# mbed-enablement-platform_F_2.net
KiCad netlist of a schematic drawn in Altium Designer
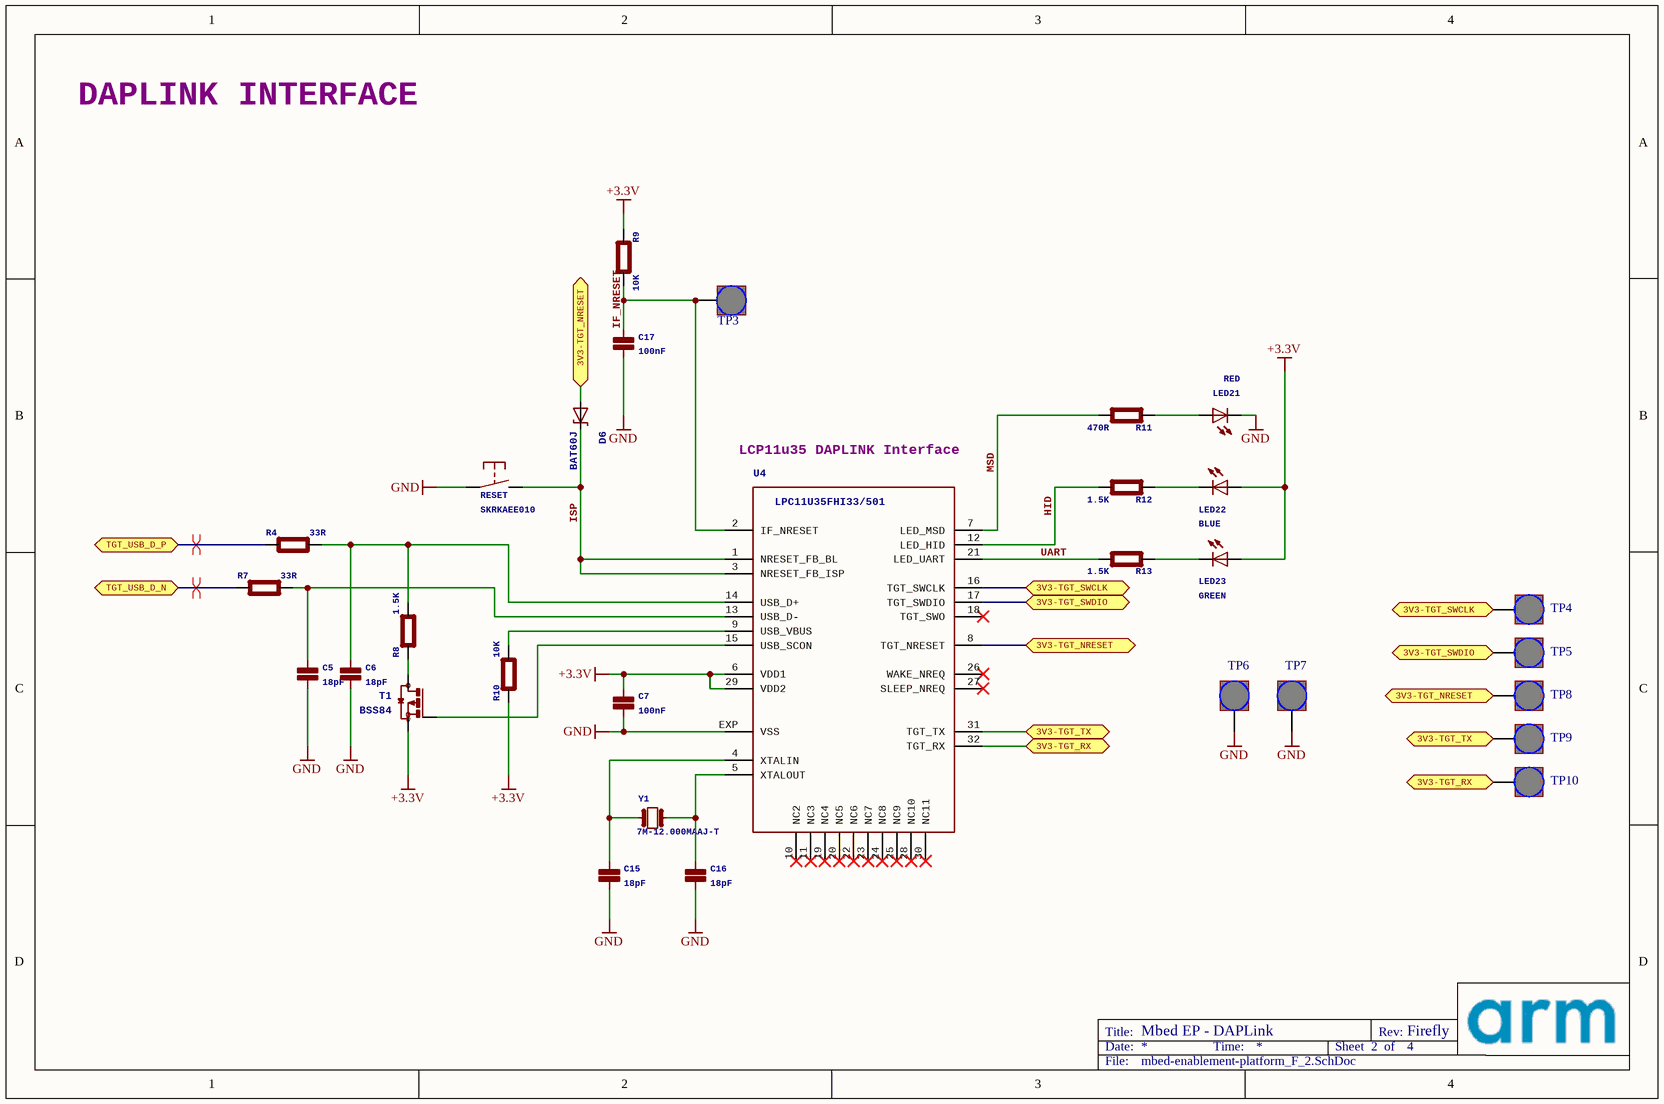
[diagram p0: mbed-enablement-platform_F_2.SchDoc]

(export (version "E")
  (design (tool "Eeschema 10.0.6"))
  (components
    (comp (ref "C5")
      (value "18pF")
      (footprint "0402")
      (description "Capacitor")
      (libsource (lib "mbed-workplace-env-mon") (part "CAPACITOR0402"))
    )
    (comp (ref "C6")
      (value "18pF")
      (footprint "0402")
      (description "Capacitor")
      (libsource (lib "mbed-workplace-env-mon") (part "CAPACITOR0402"))
    )
    (comp (ref "C7")
      (value "100nF")
      (footprint "0402")
      (description "Capacitor")
      (libsource (lib "mbed-workplace-env-mon") (part "CAPACITOR0402"))
    )
    (comp (ref "C15")
      (value "18pF")
      (footprint "0402")
      (description "Capacitor")
      (libsource (lib "mbed-workplace-env-mon") (part "CAPACITOR0402"))
    )
    (comp (ref "C16")
      (value "18pF")
      (footprint "0402")
      (description "Capacitor")
      (libsource (lib "mbed-workplace-env-mon") (part "CAPACITOR0402"))
    )
    (comp (ref "C17")
      (value "100nF")
      (footprint "0402")
      (description "Capacitor")
      (libsource (lib "mbed-workplace-env-mon") (part "CAPACITOR0402"))
    )
    (comp (ref "D6")
      (value "BAT60J")
      (footprint "SOD323")
      (description "SCHOTTKY DIODE")
      (fields (field (name "MF") "STMicroelectronics"))
      (libsource (lib "mbed-workplace-env-mon") (part "BAT60J"))
    )
    (comp (ref "LED21")
      (value "RED")
      (footprint "CHIPLED_0603")
      (description "LED SMD, Colour Red")
      (fields (field (name "MF") "Wurth Electronics Inc"))
      (libsource (lib "mbed-workplace-env-mon") (part "SMD_LED0603"))
    )
    (comp (ref "LED22")
      (value "BLUE")
      (footprint "CHIPLED_0603")
      (description "LED SMD, Colour Red")
      (fields (field (name "MF") "Wurth Electronics Inc"))
      (libsource (lib "mbed-workplace-env-mon") (part "SMD_LED0603"))
    )
    (comp (ref "LED23")
      (value "GREEN")
      (footprint "CHIPLED_0603")
      (description "LED SMD, Colour Red")
      (fields (field (name "MF") "Wurth Electronics Inc"))
      (libsource (lib "mbed-workplace-env-mon") (part "SMD_LED0603"))
    )
    (comp (ref "R4")
      (value "33R")
      (footprint "0402")
      (description "Resistor")
      (libsource (lib "mbed-workplace-env-mon") (part "RESISTOR0402"))
    )
    (comp (ref "R7")
      (value "33R")
      (footprint "0402")
      (description "Resistor")
      (libsource (lib "mbed-workplace-env-mon") (part "RESISTOR0402"))
    )
    (comp (ref "R8")
      (value "1.5K")
      (footprint "0402")
      (description "Resistor")
      (libsource (lib "mbed-workplace-env-mon") (part "RESISTOR0402"))
    )
    (comp (ref "R9")
      (value "10K")
      (footprint "0402")
      (description "Resistor")
      (libsource (lib "mbed-workplace-env-mon") (part "RESISTOR0402"))
    )
    (comp (ref "R10")
      (value "10K")
      (footprint "0402")
      (description "Resistor")
      (libsource (lib "mbed-workplace-env-mon") (part "RESISTOR0402"))
    )
    (comp (ref "R11")
      (value "470R")
      (footprint "0402")
      (description "Resistor")
      (libsource (lib "mbed-workplace-env-mon") (part "RESISTOR0402"))
    )
    (comp (ref "R12")
      (value "1.5K")
      (footprint "0402")
      (description "Resistor")
      (libsource (lib "mbed-workplace-env-mon") (part "RESISTOR0402"))
    )
    (comp (ref "R13")
      (value "1.5K")
      (footprint "0402")
      (description "Resistor")
      (libsource (lib "mbed-workplace-env-mon") (part "RESISTOR0402"))
    )
    (comp (ref "RESET")
      (value "SKRKAEE010")
      (footprint "SKRKAEE010")
      (description "MOMENTARY SWITCH PUSH VERTICAL (SPST)")
      (fields (field (name "MF") "ALPS"))
      (libsource (lib "mbed-workplace-env-mon") (part "SKRKAEE010"))
    )
    (comp (ref "T1")
      (value "BSS84")
      (footprint "SOT23-3")
      (description "MOSFET P-CHANNEL")
      (fields (field (name "MF") "Fairchild Semiconductor"))
      (libsource (lib "mbed-workplace-env-mon") (part "BSS84"))
    )
    (comp (ref "TP3")
      (value "TP, 1.5mm")
      (footprint "TP1.5")
      (description "1.5mm round test point")
      (libsource (lib "mbed-workplace-env-mon") (part "TP1.5"))
    )
    (comp (ref "TP4")
      (value "TP, 1.5mm")
      (footprint "TP1.5")
      (description "1.5mm round test point")
      (libsource (lib "mbed-workplace-env-mon") (part "TP1.5"))
    )
    (comp (ref "TP5")
      (value "TP, 1.5mm")
      (footprint "TP1.5")
      (description "1.5mm round test point")
      (libsource (lib "mbed-workplace-env-mon") (part "TP1.5"))
    )
    (comp (ref "TP6")
      (value "TP, 1.5mm")
      (footprint "TP1.5")
      (description "1.5mm round test point")
      (libsource (lib "mbed-workplace-env-mon") (part "TP1.5"))
    )
    (comp (ref "TP7")
      (value "TP, 1.5mm")
      (footprint "TP1.5")
      (description "1.5mm round test point")
      (libsource (lib "mbed-workplace-env-mon") (part "TP1.5"))
    )
    (comp (ref "TP8")
      (value "TP, 1.5mm")
      (footprint "TP1.5")
      (description "1.5mm round test point")
      (libsource (lib "mbed-workplace-env-mon") (part "TP1.5"))
    )
    (comp (ref "TP9")
      (value "TP, 1.5mm")
      (footprint "TP1.5")
      (description "1.5mm round test point")
      (libsource (lib "mbed-workplace-env-mon") (part "TP1.5"))
    )
    (comp (ref "TP10")
      (value "TP, 1.5mm")
      (footprint "TP1.5")
      (description "1.5mm round test point")
      (libsource (lib "mbed-workplace-env-mon") (part "TP1.5"))
    )
    (comp (ref "U4")
      (value "IF_LPC11U35FHI33/501")
      (footprint "HVQFN33")
      (description "CMSIS-DAP Interface : 32-bit LPC11U00 ARM Cortex M3 RISC 64KB Flash 2.5V/3.3V 33-Pin HVQFN EP")
      (fields (field (name "MF") "NXP") (field (name "LPC11U35FHI33/501") "LPC11U35FHI33/501"))
      (libsource (lib "mbed-workplace-env-mon") (part "IF_LPC11U35FHI33/501"))
    )
    (comp (ref "Y1")
      (value "7M-12.000MAAJ-T")
      (footprint "3.2X.2.5")
      (description "Crystal, TXC 12MHz Â±30ppm 18pF")
      (fields (field (name "MF") "TXC"))
      (libsource (lib "mbed-workplace-env-mon") (part "7M-12.000MAAJ-T"))
    )
  )
  (nets
    (net (code "1") (name "+3.3V") (class "Default")
      (node (ref "C7") (pin "1") (pinfunction "P$1_1") (pintype "passive"))
      (node (ref "LED22") (pin "A") (pinfunction "A_A") (pintype "passive"))
      (node (ref "LED23") (pin "A") (pinfunction "A_A") (pintype "passive"))
      (node (ref "R10") (pin "1") (pinfunction "P$1_1") (pintype "passive"))
      (node (ref "R9") (pin "1") (pinfunction "P$1_1") (pintype "passive"))
      (node (ref "T1") (pin "2") (pinfunction "S_2") (pintype "passive"))
      (node (ref "U4") (pin "29") (pinfunction "VDD2_29") (pintype "passive"))
      (node (ref "U4") (pin "6") (pinfunction "VDD1_6") (pintype "passive"))
    )
    (net (code "2") (name "/3V3-TGT_NRESET") (class "Default")
      (node (ref "D6") (pin "A") (pinfunction "A_A") (pintype "passive"))
      (node (ref "TP8") (pin "1") (pinfunction "1_1") (pintype "passive"))
      (node (ref "U4") (pin "8") (pinfunction "TGT_NRESET_8") (pintype "passive"))
    )
    (net (code "3") (name "/3V3-TGT_RX") (class "Default")
      (node (ref "TP10") (pin "1") (pinfunction "1_1") (pintype "passive"))
      (node (ref "U4") (pin "32") (pinfunction "TGT_RX_32") (pintype "passive"))
    )
    (net (code "4") (name "/3V3-TGT_SWCLK") (class "Default")
      (node (ref "TP4") (pin "1") (pinfunction "1_1") (pintype "passive"))
      (node (ref "U4") (pin "16") (pinfunction "TGT_SWCLK_16") (pintype "passive"))
    )
    (net (code "5") (name "/3V3-TGT_SWDIO") (class "Default")
      (node (ref "TP5") (pin "1") (pinfunction "1_1") (pintype "passive"))
      (node (ref "U4") (pin "17") (pinfunction "TGT_SWDIO_17") (pintype "passive"))
    )
    (net (code "6") (name "/3V3-TGT_TX") (class "Default")
      (node (ref "TP9") (pin "1") (pinfunction "1_1") (pintype "passive"))
      (node (ref "U4") (pin "31") (pinfunction "TGT_TX_31") (pintype "passive"))
    )
    (net (code "7") (name "/HID") (class "Default")
      (node (ref "R12") (pin "2") (pinfunction "P$2_2") (pintype "passive"))
      (node (ref "U4") (pin "12") (pinfunction "LED_HID_12") (pintype "passive"))
    )
    (net (code "8") (name "/IF_NRESET") (class "Default")
      (node (ref "C17") (pin "1") (pinfunction "P$1_1") (pintype "passive"))
      (node (ref "R9") (pin "2") (pinfunction "P$2_2") (pintype "passive"))
      (node (ref "TP3") (pin "1") (pinfunction "1_1") (pintype "passive"))
      (node (ref "U4") (pin "2") (pinfunction "IF_NRESET_2") (pintype "passive"))
    )
    (net (code "9") (name "/ISP") (class "Default")
      (node (ref "D6") (pin "K") (pinfunction "K_K") (pintype "passive"))
      (node (ref "RESET") (pin "P$2") (pinfunction "S_P$2") (pintype "passive"))
      (node (ref "U4") (pin "1") (pinfunction "NRESET_FB_BL_1") (pintype "passive"))
      (node (ref "U4") (pin "3") (pinfunction "NRESET_FB_ISP_3") (pintype "passive"))
    )
    (net (code "10") (name "/MSD") (class "Default")
      (node (ref "R11") (pin "2") (pinfunction "P$2_2") (pintype "passive"))
      (node (ref "U4") (pin "7") (pinfunction "LED_MSD_7") (pintype "passive"))
    )
    (net (code "11") (name "/TGT_USB_D_N") (class "Default")
      (node (ref "R7") (pin "1") (pinfunction "P$1_1") (pintype "passive"))
    )
    (net (code "12") (name "/TGT_USB_D_P") (class "Default")
      (node (ref "R4") (pin "1") (pinfunction "P$1_1") (pintype "passive"))
    )
    (net (code "13") (name "/UART") (class "Default")
      (node (ref "R13") (pin "2") (pinfunction "P$2_2") (pintype "passive"))
      (node (ref "U4") (pin "21") (pinfunction "LED_UART_21") (pintype "passive"))
    )
    (net (code "14") (name "GND") (class "Default")
      (node (ref "C15") (pin "2") (pinfunction "P$2_2") (pintype "passive"))
      (node (ref "C16") (pin "2") (pinfunction "P$2_2") (pintype "passive"))
      (node (ref "C17") (pin "2") (pinfunction "P$2_2") (pintype "passive"))
      (node (ref "C5") (pin "2") (pinfunction "P$2_2") (pintype "passive"))
      (node (ref "C6") (pin "2") (pinfunction "P$2_2") (pintype "passive"))
      (node (ref "C7") (pin "2") (pinfunction "P$2_2") (pintype "passive"))
      (node (ref "LED21") (pin "C") (pinfunction "C_C") (pintype "passive"))
      (node (ref "RESET") (pin "P$1") (pinfunction "P_P$1") (pintype "passive"))
      (node (ref "TP6") (pin "1") (pinfunction "1_1") (pintype "passive"))
      (node (ref "TP7") (pin "1") (pinfunction "1_1") (pintype "passive"))
      (node (ref "U4") (pin "EXP") (pinfunction "VSS_EXP") (pintype "passive"))
    )
    (net (code "15") (name "Net-(C5-P$1)") (class "Default")
      (node (ref "C5") (pin "1") (pinfunction "P$1_1") (pintype "passive"))
      (node (ref "R7") (pin "2") (pinfunction "P$2_2") (pintype "passive"))
      (node (ref "U4") (pin "13") (pinfunction "USB_D-_13") (pintype "passive"))
    )
    (net (code "16") (name "Net-(C6-P$1)") (class "Default")
      (node (ref "C6") (pin "1") (pinfunction "P$1_1") (pintype "passive"))
      (node (ref "R4") (pin "2") (pinfunction "P$2_2") (pintype "passive"))
      (node (ref "R8") (pin "2") (pinfunction "P$2_2") (pintype "passive"))
      (node (ref "U4") (pin "14") (pinfunction "USB_D+_14") (pintype "passive"))
    )
    (net (code "17") (name "Net-(C15-P$1)") (class "Default")
      (node (ref "C15") (pin "1") (pinfunction "P$1_1") (pintype "passive"))
      (node (ref "U4") (pin "4") (pinfunction "XTALIN_4") (pintype "passive"))
      (node (ref "Y1") (pin "P$1") (pinfunction "1_P$1") (pintype "passive"))
    )
    (net (code "18") (name "Net-(C16-P$1)") (class "Default")
      (node (ref "C16") (pin "1") (pinfunction "P$1_1") (pintype "passive"))
      (node (ref "U4") (pin "5") (pinfunction "XTALOUT_5") (pintype "passive"))
      (node (ref "Y1") (pin "P$3") (pinfunction "2_P$3") (pintype "passive"))
    )
    (net (code "19") (name "Net-(R8-P$1)") (class "Default")
      (node (ref "R8") (pin "1") (pinfunction "P$1_1") (pintype "passive"))
      (node (ref "T1") (pin "3") (pinfunction "D_3") (pintype "passive"))
    )
    (net (code "20") (name "Net-(R10-P$2)") (class "Default")
      (node (ref "R10") (pin "2") (pinfunction "P$2_2") (pintype "passive"))
      (node (ref "U4") (pin "9") (pinfunction "USB_VBUS_9") (pintype "passive"))
    )
    (net (code "21") (name "Net-(R11-P$1)") (class "Default")
      (node (ref "LED21") (pin "A") (pinfunction "A_A") (pintype "passive"))
      (node (ref "R11") (pin "1") (pinfunction "P$1_1") (pintype "passive"))
    )
    (net (code "22") (name "Net-(R12-P$1)") (class "Default")
      (node (ref "LED22") (pin "C") (pinfunction "C_C") (pintype "passive"))
      (node (ref "R12") (pin "1") (pinfunction "P$1_1") (pintype "passive"))
    )
    (net (code "23") (name "Net-(R13-P$1)") (class "Default")
      (node (ref "LED23") (pin "C") (pinfunction "C_C") (pintype "passive"))
      (node (ref "R13") (pin "1") (pinfunction "P$1_1") (pintype "passive"))
    )
    (net (code "24") (name "Net-(T1-G)") (class "Default")
      (node (ref "T1") (pin "1") (pinfunction "G_1") (pintype "passive"))
      (node (ref "U4") (pin "15") (pinfunction "USB_SCON_15") (pintype "passive"))
    )
    (net (code "25") (name "unconnected-(U4-NC2-Pad10)") (class "Default")
      (node (ref "U4") (pin "10") (pinfunction "NC2_10") (pintype "passive+no_connect"))
    )
    (net (code "26") (name "unconnected-(U4-NC3-Pad11)") (class "Default")
      (node (ref "U4") (pin "11") (pinfunction "NC3_11") (pintype "passive+no_connect"))
    )
    (net (code "27") (name "unconnected-(U4-NC4-Pad19)") (class "Default")
      (node (ref "U4") (pin "19") (pinfunction "NC4_19") (pintype "passive+no_connect"))
    )
    (net (code "28") (name "unconnected-(U4-NC5-Pad20)") (class "Default")
      (node (ref "U4") (pin "20") (pinfunction "NC5_20") (pintype "passive+no_connect"))
    )
    (net (code "29") (name "unconnected-(U4-NC6-Pad22)") (class "Default")
      (node (ref "U4") (pin "22") (pinfunction "NC6_22") (pintype "passive+no_connect"))
    )
    (net (code "30") (name "unconnected-(U4-NC7-Pad23)") (class "Default")
      (node (ref "U4") (pin "23") (pinfunction "NC7_23") (pintype "passive+no_connect"))
    )
    (net (code "31") (name "unconnected-(U4-NC8-Pad24)") (class "Default")
      (node (ref "U4") (pin "24") (pinfunction "NC8_24") (pintype "passive+no_connect"))
    )
    (net (code "32") (name "unconnected-(U4-NC9-Pad25)") (class "Default")
      (node (ref "U4") (pin "25") (pinfunction "NC9_25") (pintype "passive+no_connect"))
    )
    (net (code "33") (name "unconnected-(U4-NC10-Pad28)") (class "Default")
      (node (ref "U4") (pin "28") (pinfunction "NC10_28") (pintype "passive+no_connect"))
    )
    (net (code "34") (name "unconnected-(U4-NC11-Pad30)") (class "Default")
      (node (ref "U4") (pin "30") (pinfunction "NC11_30") (pintype "passive+no_connect"))
    )
    (net (code "35") (name "unconnected-(U4-SLEEP_NREQ-Pad27)") (class "Default")
      (node (ref "U4") (pin "27") (pinfunction "SLEEP_NREQ_27") (pintype "passive+no_connect"))
    )
    (net (code "36") (name "unconnected-(U4-TGT_SWO-Pad18)") (class "Default")
      (node (ref "U4") (pin "18") (pinfunction "TGT_SWO_18") (pintype "passive+no_connect"))
    )
    (net (code "37") (name "unconnected-(U4-WAKE_NREQ-Pad26)") (class "Default")
      (node (ref "U4") (pin "26") (pinfunction "WAKE_NREQ_26") (pintype "passive+no_connect"))
    )
  )
)
